# ESPblaster.net
KiCad netlist of a schematic drawn in EAGLE
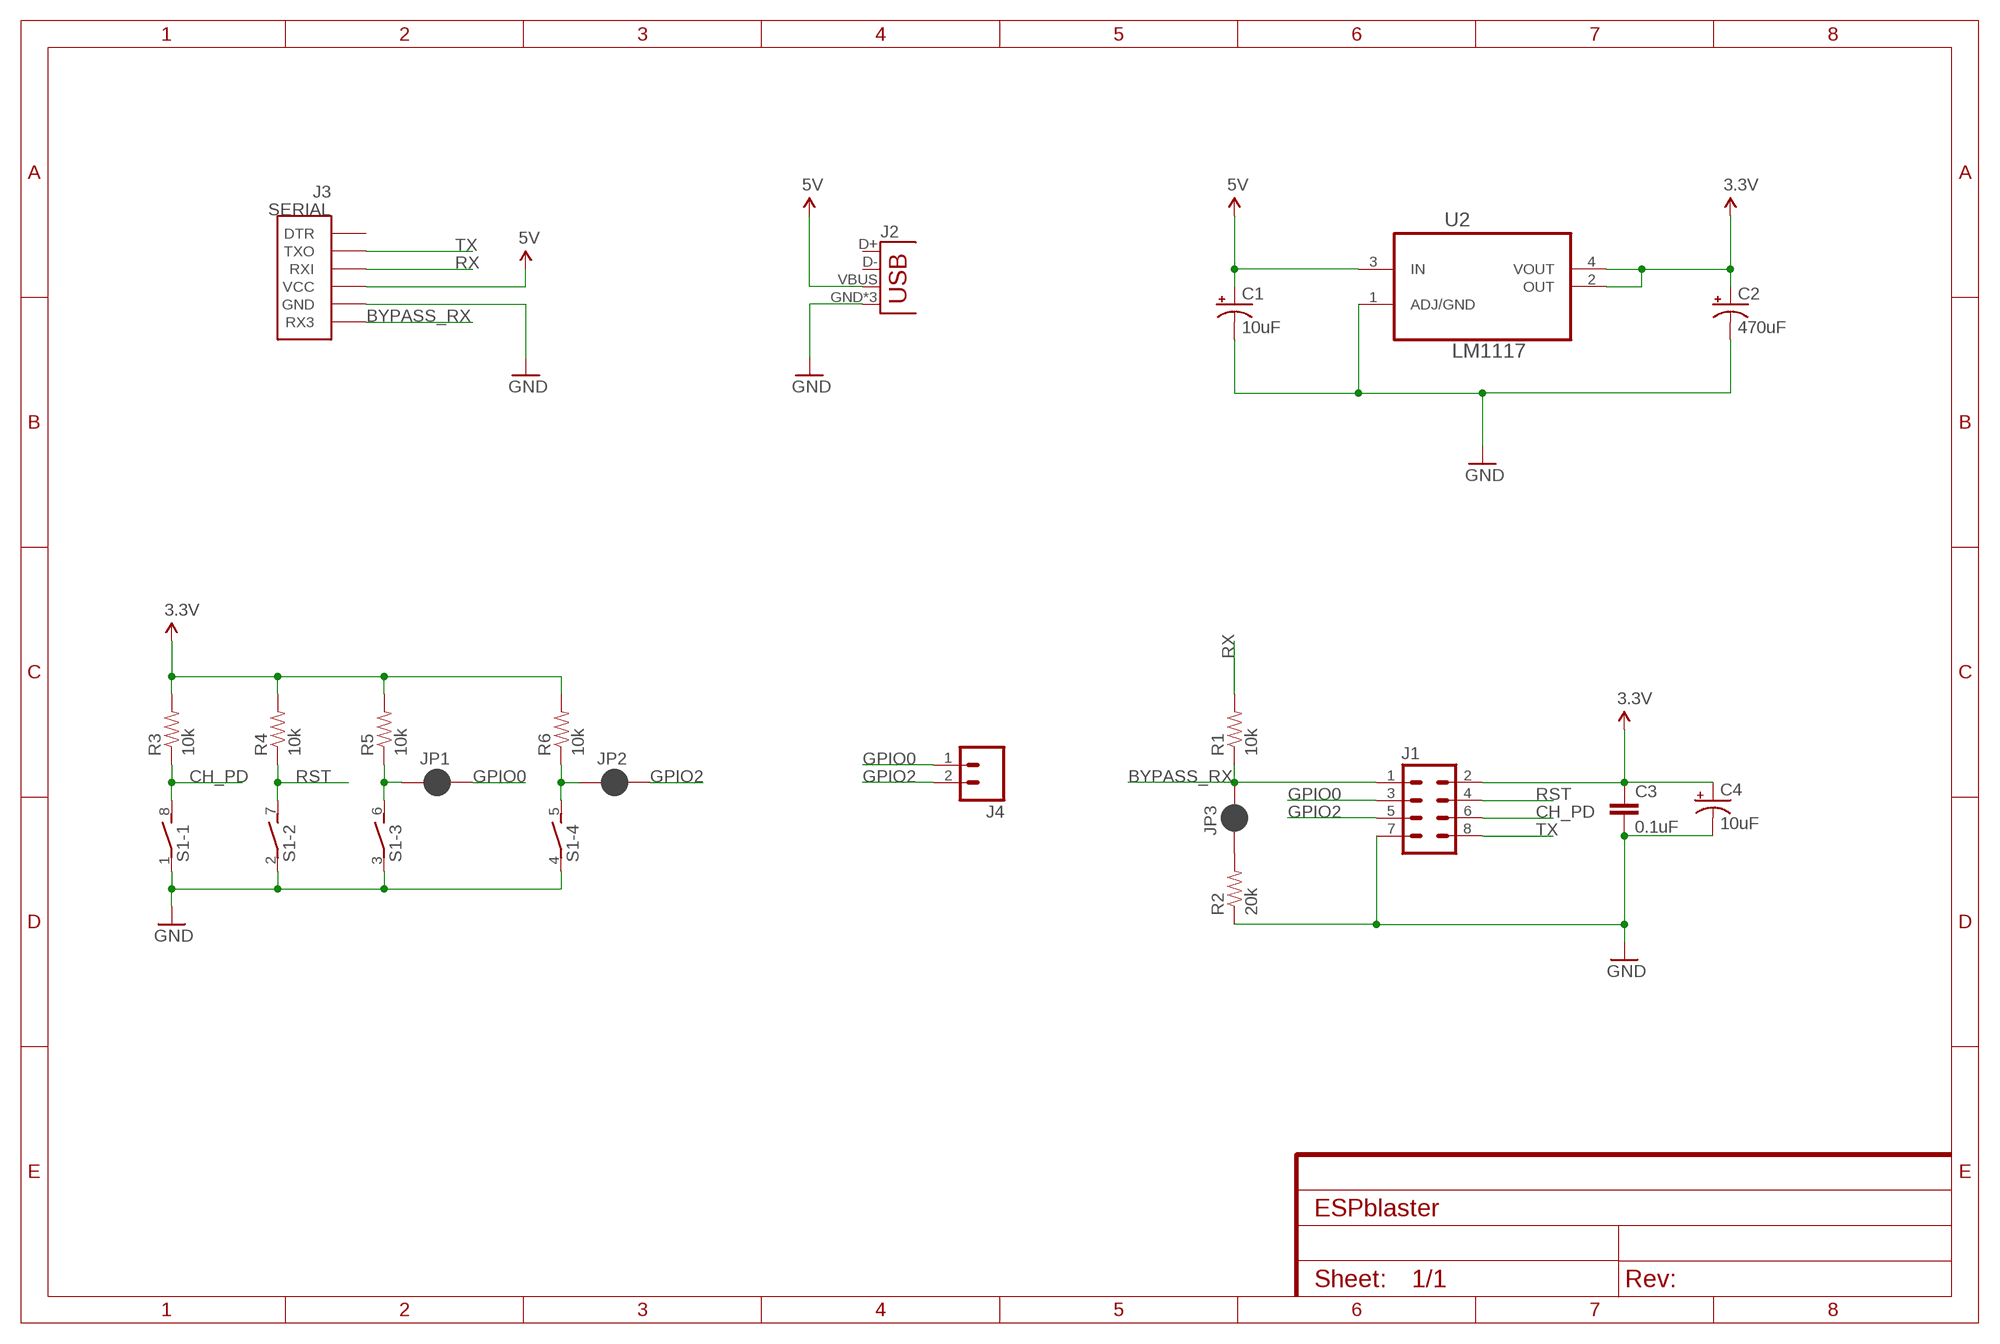
[diagram p0: schematic, sheet 1]

(export (version "E")
  (design (tool "Eeschema 10.0.6"))
  (components
    (comp (ref "C1")
      (value "10uF")
      (footprint "eagle-import:EIA3216-KIT")
      (libsource (lib "eagle-import") (part "CAP_POL1206-KIT"))
    )
    (comp (ref "C2")
      (value "470uF")
      (footprint "eagle-import:CPOL-RADIAL-100UF-25V")
      (libsource (lib "eagle-import") (part "CAP_POLPTH1"))
    )
    (comp (ref "C3")
      (value "0.1uF")
      (footprint "eagle-import:1206")
      (libsource (lib "eagle-import") (part "CAP1206"))
    )
    (comp (ref "C4")
      (value "10uF")
      (footprint "eagle-import:EIA3216-KIT")
      (libsource (lib "eagle-import") (part "CAP_POL1206-KIT"))
    )
    (comp (ref "J1")
      (value "M04X2")
      (footprint "eagle-import:2X4")
      (libsource (lib "eagle-import") (part "M04X2"))
    )
    (comp (ref "J2")
      (value "USB-MICROB")
      (footprint "eagle-import:USB-MICROB")
      (libsource (lib "eagle-import") (part "USB-MICROB"))
    )
    (comp (ref "J3")
      (value "SERIAL")
      (footprint "eagle-import:CP2102_DEVICE_SIDE_ESP8266")
      (libsource (lib "eagle-import") (part "CP2102_DEVICE_ESP8266CP2"))
    )
    (comp (ref "J4")
      (value "M02LOCK")
      (footprint "eagle-import:1X02_LOCK")
      (libsource (lib "eagle-import") (part "M02LOCK"))
    )
    (comp (ref "JP1")
      (value "JUMPER-PAD-2-NC_BY_PASTEFULL-BOX-SILK")
      (footprint "eagle-import:PAD-JUMPER-2-NC_BY_PASTE_YES_SILK_FULL_BOX")
      (libsource (lib "eagle-import") (part "JUMPER-PAD-2-NC_BY_PASTEFULL-BOX-SILK"))
    )
    (comp (ref "JP2")
      (value "JUMPER-PAD-2-NC_BY_PASTEFULL-BOX-SILK")
      (footprint "eagle-import:PAD-JUMPER-2-NC_BY_PASTE_YES_SILK_FULL_BOX")
      (libsource (lib "eagle-import") (part "JUMPER-PAD-2-NC_BY_PASTEFULL-BOX-SILK"))
    )
    (comp (ref "JP3")
      (value "JUMPER-PAD-2-NC_BY_PASTEFULL-BOX-SILK")
      (footprint "eagle-import:PAD-JUMPER-2-NC_BY_PASTE_YES_SILK_FULL_BOX")
      (libsource (lib "eagle-import") (part "JUMPER-PAD-2-NC_BY_PASTEFULL-BOX-SILK"))
    )
    (comp (ref "R1")
      (value "10k")
      (footprint "eagle-import:1206")
      (libsource (lib "eagle-import") (part "RESISTOR1206"))
    )
    (comp (ref "R2")
      (value "20k")
      (footprint "eagle-import:1206")
      (libsource (lib "eagle-import") (part "RESISTOR1206"))
    )
    (comp (ref "R3")
      (value "10k")
      (footprint "eagle-import:1206")
      (libsource (lib "eagle-import") (part "RESISTOR1206"))
    )
    (comp (ref "R4")
      (value "10k")
      (footprint "eagle-import:1206")
      (libsource (lib "eagle-import") (part "RESISTOR1206"))
    )
    (comp (ref "R5")
      (value "10k")
      (footprint "eagle-import:1206")
      (libsource (lib "eagle-import") (part "RESISTOR1206"))
    )
    (comp (ref "R6")
      (value "10k")
      (footprint "eagle-import:1206")
      (libsource (lib "eagle-import") (part "RESISTOR1206"))
    )
    (comp (ref "S1")
      (value "DIP04S")
      (footprint "eagle-import:DIP04S")
      (libsource (lib "eagle-import") (part "DIP04S"))
    )
    (comp (ref "U2")
      (value "LM1117")
      (footprint "eagle-import:SOT230P696X180-4N")
      (fields (field (name "MPN") "LM1117MP-3.3"))
      (libsource (lib "eagle-import") (part "LM1117MP-3.3"))
    )
  )
  (nets
    (net (code "1") (name "/BYPASS_RX") (class "Default")
      (node (ref "J1") (pin "1") (pinfunction "1_1") (pintype "passive"))
      (node (ref "J3") (pin "P$6") (pinfunction "RX3_P$6") (pintype "bidirectional"))
      (node (ref "JP3") (pin "2") (pinfunction "2_2") (pintype "passive"))
      (node (ref "R1") (pin "1") (pinfunction "1_1") (pintype "passive"))
    )
    (net (code "2") (name "/CH_PD") (class "Default")
      (node (ref "J1") (pin "6") (pinfunction "6_6") (pintype "passive"))
      (node (ref "R3") (pin "1") (pinfunction "1_1") (pintype "passive"))
      (node (ref "S1") (pin "8") (pinfunction "2_8") (pintype "passive"))
    )
    (net (code "3") (name "/GPIO0") (class "Default")
      (node (ref "J1") (pin "3") (pinfunction "3_3") (pintype "passive"))
      (node (ref "J4") (pin "1") (pinfunction "1_1") (pintype "passive"))
      (node (ref "JP1") (pin "2") (pinfunction "2_2") (pintype "passive"))
    )
    (net (code "4") (name "/GPIO2") (class "Default")
      (node (ref "J1") (pin "5") (pinfunction "5_5") (pintype "passive"))
      (node (ref "J4") (pin "2") (pinfunction "2_2") (pintype "passive"))
      (node (ref "JP2") (pin "2") (pinfunction "2_2") (pintype "passive"))
    )
    (net (code "5") (name "/RST") (class "Default")
      (node (ref "J1") (pin "4") (pinfunction "4_4") (pintype "passive"))
      (node (ref "R4") (pin "1") (pinfunction "1_1") (pintype "passive"))
      (node (ref "S1") (pin "7") (pinfunction "2_7") (pintype "passive"))
    )
    (net (code "6") (name "/RX") (class "Default")
      (node (ref "J3") (pin "P$3") (pinfunction "RXI_P$3") (pintype "bidirectional"))
      (node (ref "R1") (pin "2") (pinfunction "2_2") (pintype "passive"))
    )
    (net (code "7") (name "/TX") (class "Default")
      (node (ref "J1") (pin "8") (pinfunction "8_8") (pintype "passive"))
      (node (ref "J3") (pin "P$2") (pinfunction "TXO_P$2") (pintype "bidirectional"))
    )
    (net (code "8") (name "3.3V") (class "Default")
      (node (ref "C2") (pin "1") (pinfunction "+_1") (pintype "passive"))
      (node (ref "C3") (pin "1") (pinfunction "1_1") (pintype "passive"))
      (node (ref "C4") (pin "A") (pinfunction "+_A") (pintype "passive"))
      (node (ref "J1") (pin "2") (pinfunction "2_2") (pintype "passive"))
      (node (ref "R3") (pin "2") (pinfunction "2_2") (pintype "passive"))
      (node (ref "R4") (pin "2") (pinfunction "2_2") (pintype "passive"))
      (node (ref "R5") (pin "2") (pinfunction "2_2") (pintype "passive"))
      (node (ref "R6") (pin "2") (pinfunction "2_2") (pintype "passive"))
      (node (ref "U2") (pin "2") (pinfunction "OUT_2") (pintype "output"))
      (node (ref "U2") (pin "4") (pinfunction "VOUT_4") (pintype "output"))
    )
    (net (code "9") (name "5V") (class "Default")
      (node (ref "C1") (pin "A") (pinfunction "+_A") (pintype "passive"))
      (node (ref "J2") (pin "VBUS") (pinfunction "VBUS_VBUS") (pintype "bidirectional"))
      (node (ref "J3") (pin "P$4") (pinfunction "VCC_P$4") (pintype "bidirectional"))
      (node (ref "U2") (pin "3") (pinfunction "IN_3") (pintype "input"))
    )
    (net (code "10") (name "GND") (class "Default")
      (node (ref "C1") (pin "C") (pinfunction "-_C") (pintype "passive"))
      (node (ref "C2") (pin "2") (pinfunction "-_2") (pintype "passive"))
      (node (ref "C3") (pin "2") (pinfunction "2_2") (pintype "passive"))
      (node (ref "C4") (pin "C") (pinfunction "-_C") (pintype "passive"))
      (node (ref "J1") (pin "7") (pinfunction "7_7") (pintype "passive"))
      (node (ref "J2") (pin "GND") (pinfunction "GND_GND") (pintype "bidirectional"))
      (node (ref "J2") (pin "MT1") (pinfunction "GND_MT1") (pintype "bidirectional"))
      (node (ref "J2") (pin "MT2") (pinfunction "GND_MT2") (pintype "bidirectional"))
      (node (ref "J3") (pin "P$5") (pinfunction "GND_P$5") (pintype "bidirectional"))
      (node (ref "R2") (pin "1") (pinfunction "1_1") (pintype "passive"))
      (node (ref "S1") (pin "1") (pinfunction "1_1") (pintype "passive"))
      (node (ref "S1") (pin "2") (pinfunction "1_2") (pintype "passive"))
      (node (ref "S1") (pin "3") (pinfunction "1_3") (pintype "passive"))
      (node (ref "S1") (pin "4") (pinfunction "1_4") (pintype "passive"))
      (node (ref "U2") (pin "1") (pinfunction "ADJ/GND_1") (pintype "passive"))
    )
    (net (code "11") (name "Net-(JP3-Pad1)") (class "Default")
      (node (ref "JP3") (pin "1") (pinfunction "1_1") (pintype "passive"))
      (node (ref "R2") (pin "2") (pinfunction "2_2") (pintype "passive"))
    )
    (net (code "12") (name "Net-(S1C-2)") (class "Default")
      (node (ref "JP1") (pin "1") (pinfunction "1_1") (pintype "passive"))
      (node (ref "R5") (pin "1") (pinfunction "1_1") (pintype "passive"))
      (node (ref "S1") (pin "6") (pinfunction "2_6") (pintype "passive"))
    )
    (net (code "13") (name "Net-(S1D-2)") (class "Default")
      (node (ref "JP2") (pin "1") (pinfunction "1_1") (pintype "passive"))
      (node (ref "R6") (pin "1") (pinfunction "1_1") (pintype "passive"))
      (node (ref "S1") (pin "5") (pinfunction "2_5") (pintype "passive"))
    )
    (net (code "14") (name "unconnected-(J2-PadD+)") (class "Default")
      (node (ref "J2") (pin "D+") (pinfunction "D+_D+") (pintype "bidirectional"))
    )
    (net (code "15") (name "unconnected-(J2-PadD-)") (class "Default")
      (node (ref "J2") (pin "D-") (pinfunction "D-_D-") (pintype "bidirectional"))
    )
    (net (code "16") (name "unconnected-(J3-DTR-PadP$1)") (class "Default")
      (node (ref "J3") (pin "P$1") (pinfunction "DTR_P$1") (pintype "bidirectional"))
    )
  )
)
